# pendulum_encoder_board.net
KiCad netlist of a schematic drawn in EAGLE
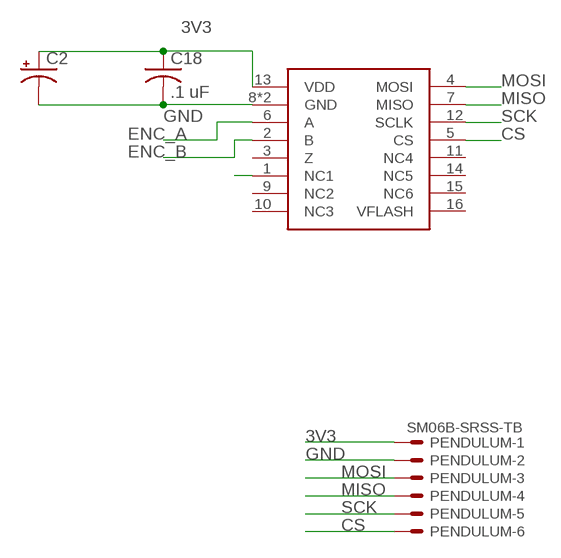
[diagram p0: schematic, sheet 1]

(export (version "E")
  (design (tool "Eeschema 10.0.6"))
  (components
    (comp (ref "C2")
      (value "CPOL-USE2.5-5")
      (footprint "eagle-import:E2,5-5")
      (libsource (lib "eagle-import") (part "CPOL-USE2.5-5"))
    )
    (comp (ref "C18")
      (value ".1 uF")
      (footprint "eagle-import:C0402K")
      (libsource (lib "eagle-import") (part "C-USC0402K"))
    )
    (comp (ref "PENDULUM")
      (value "SM06B-SRSS-TB")
      (footprint "eagle-import:SM06B-SRSS-TB")
      (libsource (lib "eagle-import") (part "?M06B-SRSS-TBS"))
    )
    (comp (ref "U$11")
      (value "MA700")
      (footprint "eagle-import:QFN16")
      (libsource (lib "eagle-import") (part "MA700"))
    )
  )
  (nets
    (net (code "1") (name "/3V3") (class "Default")
      (node (ref "C18") (pin "1") (pinfunction "1_1") (pintype "passive"))
      (node (ref "C2") (pin "+") (pinfunction "+_+") (pintype "passive"))
      (node (ref "PENDULUM") (pin "1") (pinfunction "S_1") (pintype "passive"))
      (node (ref "U$11") (pin "13") (pinfunction "VDD_13") (pintype "bidirectional"))
    )
    (net (code "2") (name "/CS") (class "Default")
      (node (ref "PENDULUM") (pin "6") (pinfunction "S_6") (pintype "passive"))
      (node (ref "U$11") (pin "5") (pinfunction "CS_5") (pintype "bidirectional"))
    )
    (net (code "3") (name "/ENC_A") (class "Default")
      (node (ref "U$11") (pin "6") (pinfunction "A_6") (pintype "bidirectional"))
    )
    (net (code "4") (name "/ENC_B") (class "Default")
      (node (ref "U$11") (pin "2") (pinfunction "B_2") (pintype "bidirectional"))
    )
    (net (code "5") (name "/GND") (class "Default")
      (node (ref "C18") (pin "2") (pinfunction "2_2") (pintype "passive"))
      (node (ref "C2") (pin "-") (pinfunction "-_-") (pintype "passive"))
      (node (ref "PENDULUM") (pin "2") (pinfunction "S_2") (pintype "passive"))
      (node (ref "U$11") (pin "8") (pinfunction "GND_8") (pintype "bidirectional"))
      (node (ref "U$11") (pin "TH") (pinfunction "GND_TH") (pintype "bidirectional"))
    )
    (net (code "6") (name "/MISO") (class "Default")
      (node (ref "PENDULUM") (pin "4") (pinfunction "S_4") (pintype "passive"))
      (node (ref "U$11") (pin "7") (pinfunction "MISO_7") (pintype "bidirectional"))
    )
    (net (code "7") (name "/MOSI") (class "Default")
      (node (ref "PENDULUM") (pin "3") (pinfunction "S_3") (pintype "passive"))
      (node (ref "U$11") (pin "4") (pinfunction "MOSI_4") (pintype "bidirectional"))
    )
    (net (code "8") (name "/SCK") (class "Default")
      (node (ref "PENDULUM") (pin "5") (pinfunction "S_5") (pintype "passive"))
      (node (ref "U$11") (pin "12") (pinfunction "SCLK_12") (pintype "bidirectional"))
    )
    (net (code "9") (name "unconnected-(U$11-NC1-Pad1)") (class "Default")
      (node (ref "U$11") (pin "1") (pinfunction "NC1_1") (pintype "bidirectional"))
    )
    (net (code "10") (name "unconnected-(U$11-NC2-Pad9)") (class "Default")
      (node (ref "U$11") (pin "9") (pinfunction "NC2_9") (pintype "bidirectional"))
    )
    (net (code "11") (name "unconnected-(U$11-NC3-Pad10)") (class "Default")
      (node (ref "U$11") (pin "10") (pinfunction "NC3_10") (pintype "bidirectional"))
    )
    (net (code "12") (name "unconnected-(U$11-NC4-Pad11)") (class "Default")
      (node (ref "U$11") (pin "11") (pinfunction "NC4_11") (pintype "bidirectional"))
    )
    (net (code "13") (name "unconnected-(U$11-NC5-Pad14)") (class "Default")
      (node (ref "U$11") (pin "14") (pinfunction "NC5_14") (pintype "bidirectional"))
    )
    (net (code "14") (name "unconnected-(U$11-NC6-Pad15)") (class "Default")
      (node (ref "U$11") (pin "15") (pinfunction "NC6_15") (pintype "bidirectional"))
    )
    (net (code "15") (name "unconnected-(U$11-VFLASH-Pad16)") (class "Default")
      (node (ref "U$11") (pin "16") (pinfunction "VFLASH_16") (pintype "bidirectional"))
    )
    (net (code "16") (name "unconnected-(U$11-Z-Pad3)") (class "Default")
      (node (ref "U$11") (pin "3") (pinfunction "Z_3") (pintype "bidirectional"))
    )
  )
)
